# cryobondr-qbit2-aqc-rev2.net
KiCad netlist of a schematic drawn in EAGLE
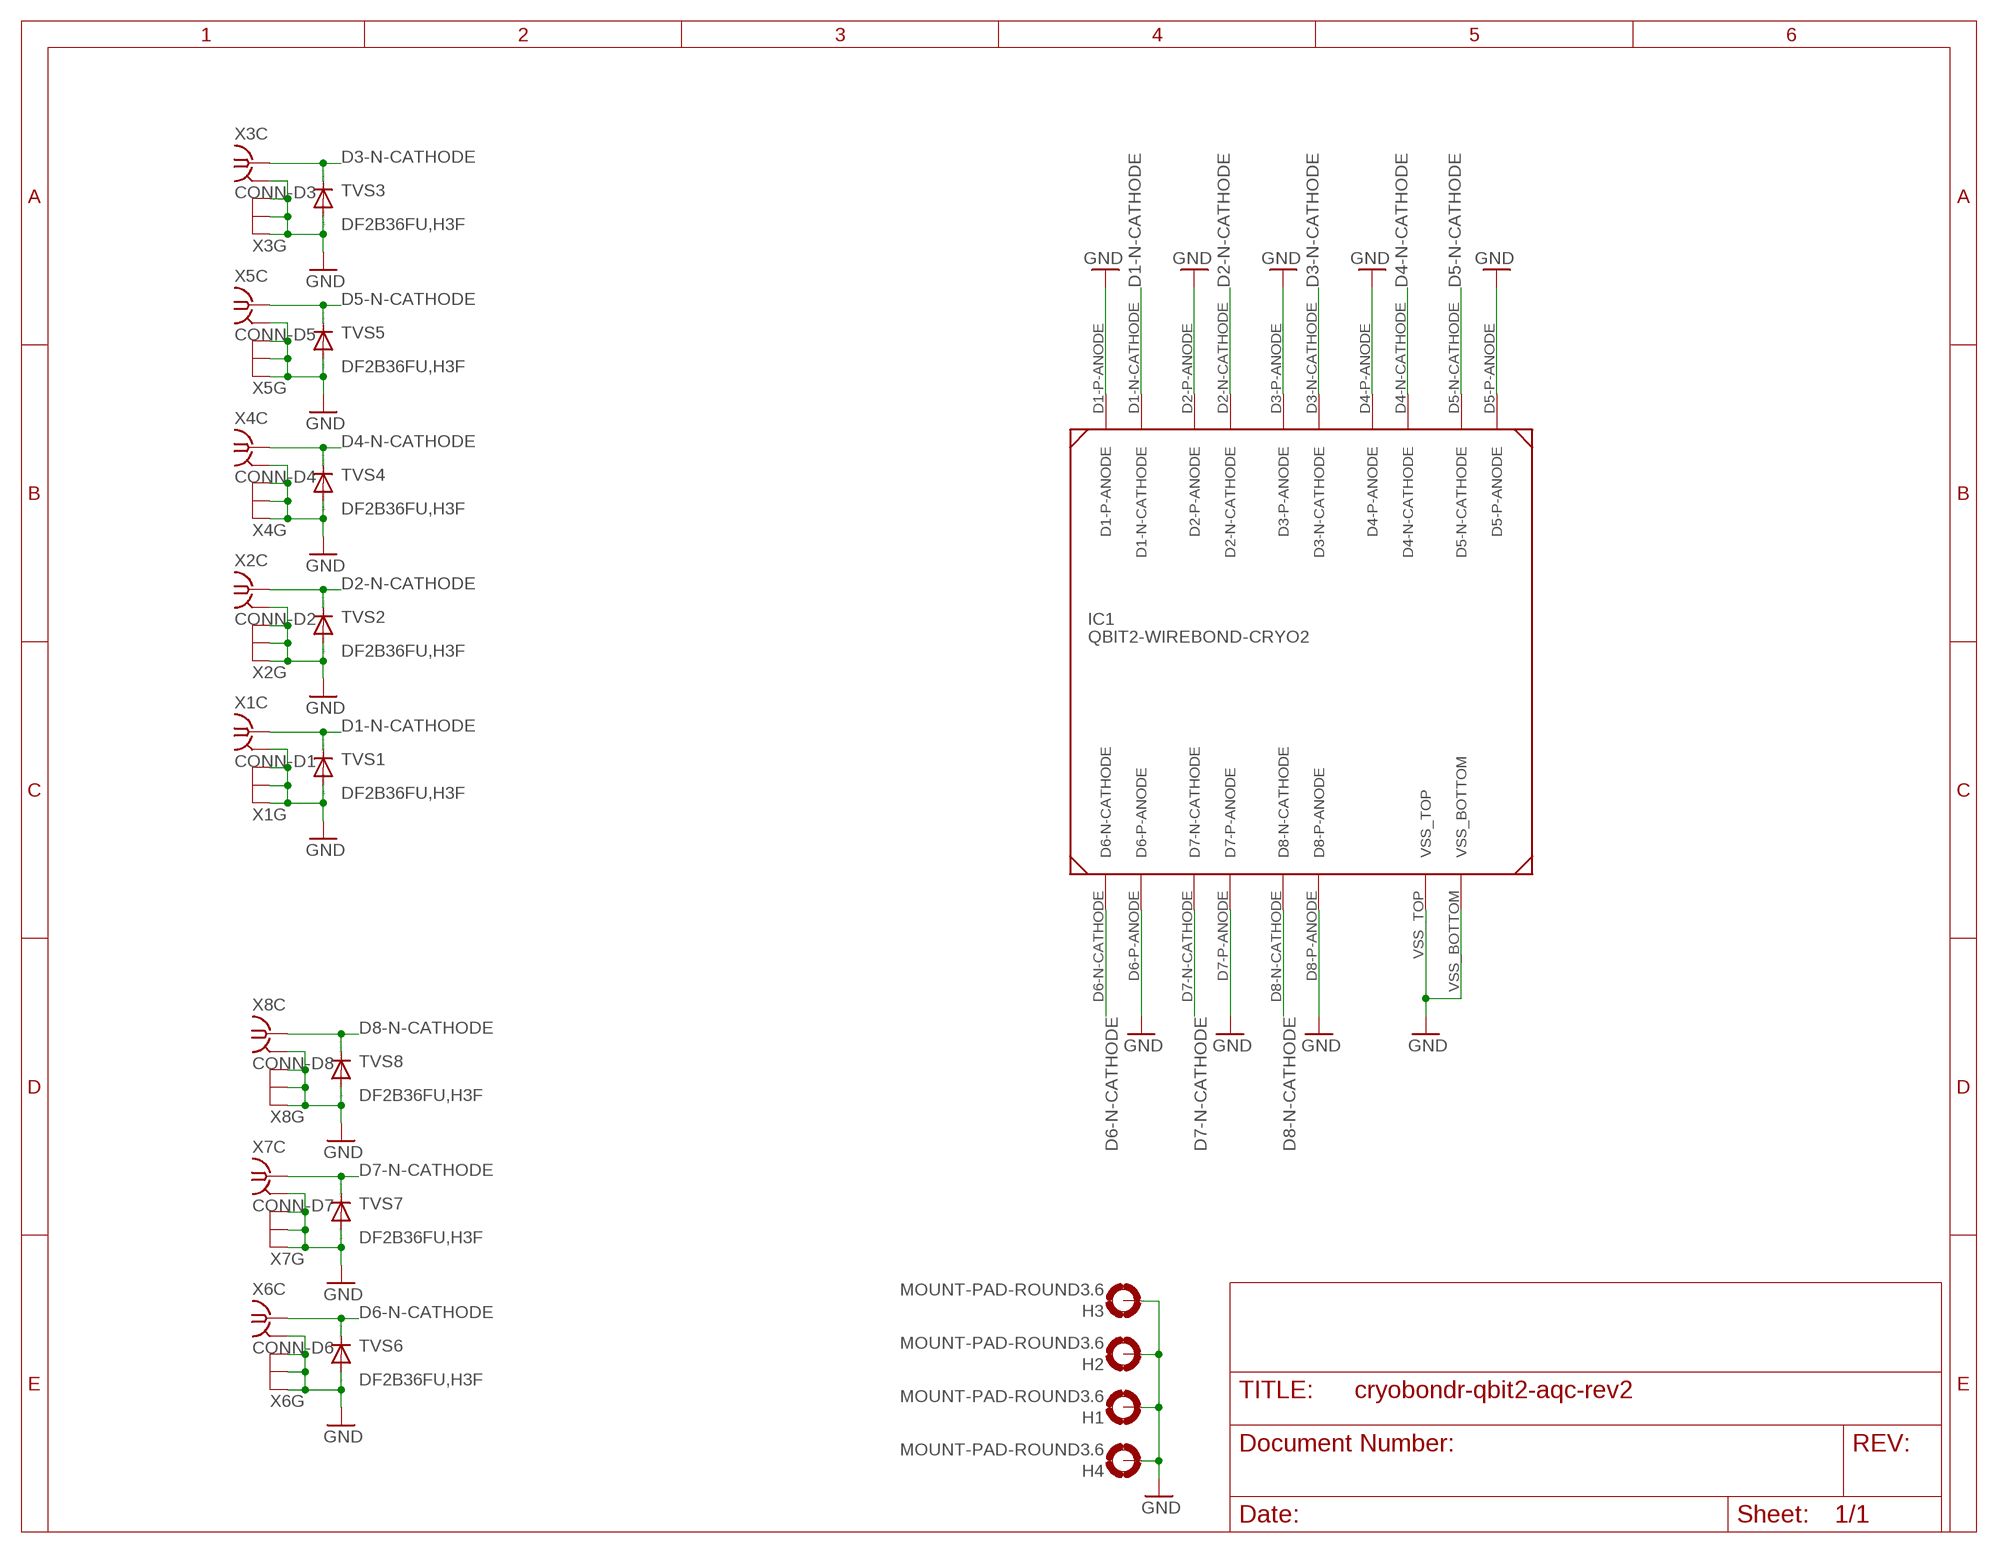
[diagram p0: schematic, sheet 1]

(export (version "E")
  (design (tool "Eeschema 10.0.6"))
  (components
    (comp (ref "H1")
      (value "MOUNT-PAD-ROUND3.6")
      (footprint "eagle-import:3,6-PAD")
      (libsource (lib "eagle-import") (part "MOUNT-PAD-ROUND3.6"))
    )
    (comp (ref "H2")
      (value "MOUNT-PAD-ROUND3.6")
      (footprint "eagle-import:3,6-PAD")
      (libsource (lib "eagle-import") (part "MOUNT-PAD-ROUND3.6"))
    )
    (comp (ref "H3")
      (value "MOUNT-PAD-ROUND3.6")
      (footprint "eagle-import:3,6-PAD")
      (libsource (lib "eagle-import") (part "MOUNT-PAD-ROUND3.6"))
    )
    (comp (ref "H4")
      (value "MOUNT-PAD-ROUND3.6")
      (footprint "eagle-import:3,6-PAD")
      (libsource (lib "eagle-import") (part "MOUNT-PAD-ROUND3.6"))
    )
    (comp (ref "IC1")
      (value "QBIT2-WIREBOND-CRYO2")
      (footprint "eagle-import:QBIT2-WIREBOND-CRYO2")
      (libsource (lib "eagle-import") (part "QBIT2-WIREBOND-CRYO2"))
    )
    (comp (ref "TVS1")
      (value "DF2B36FU,H3F")
      (footprint "eagle-import:SOD323-R")
      (libsource (lib "eagle-import") (part "DIODE-SOD323-R"))
    )
    (comp (ref "TVS2")
      (value "DF2B36FU,H3F")
      (footprint "eagle-import:SOD323-R")
      (libsource (lib "eagle-import") (part "DIODE-SOD323-R"))
    )
    (comp (ref "TVS3")
      (value "DF2B36FU,H3F")
      (footprint "eagle-import:SOD323-R")
      (libsource (lib "eagle-import") (part "DIODE-SOD323-R"))
    )
    (comp (ref "TVS4")
      (value "DF2B36FU,H3F")
      (footprint "eagle-import:SOD323-R")
      (libsource (lib "eagle-import") (part "DIODE-SOD323-R"))
    )
    (comp (ref "TVS5")
      (value "DF2B36FU,H3F")
      (footprint "eagle-import:SOD323-R")
      (libsource (lib "eagle-import") (part "DIODE-SOD323-R"))
    )
    (comp (ref "TVS6")
      (value "DF2B36FU,H3F")
      (footprint "eagle-import:SOD323-R")
      (libsource (lib "eagle-import") (part "DIODE-SOD323-R"))
    )
    (comp (ref "TVS7")
      (value "DF2B36FU,H3F")
      (footprint "eagle-import:SOD323-R")
      (libsource (lib "eagle-import") (part "DIODE-SOD323-R"))
    )
    (comp (ref "TVS8")
      (value "DF2B36FU,H3F")
      (footprint "eagle-import:SOD323-R")
      (libsource (lib "eagle-import") (part "DIODE-SOD323-R"))
    )
    (comp (ref "X1")
      (value "CONN-D1")
      (footprint "eagle-import:MMCX-SMT-BIGPADS")
      (libsource (lib "eagle-import") (part "MMCXBIGPAD"))
    )
    (comp (ref "X2")
      (value "CONN-D2")
      (footprint "eagle-import:MMCX-SMT-BIGPADS")
      (libsource (lib "eagle-import") (part "MMCXBIGPAD"))
    )
    (comp (ref "X3")
      (value "CONN-D3")
      (footprint "eagle-import:MMCX-SMT-BIGPADS")
      (libsource (lib "eagle-import") (part "MMCXBIGPAD"))
    )
    (comp (ref "X4")
      (value "CONN-D4")
      (footprint "eagle-import:MMCX-SMT-BIGPADS")
      (libsource (lib "eagle-import") (part "MMCXBIGPAD"))
    )
    (comp (ref "X5")
      (value "CONN-D5")
      (footprint "eagle-import:MMCX-SMT-BIGPADS")
      (libsource (lib "eagle-import") (part "MMCXBIGPAD"))
    )
    (comp (ref "X6")
      (value "CONN-D6")
      (footprint "eagle-import:MMCX-SMT-BIGPADS")
      (libsource (lib "eagle-import") (part "MMCXBIGPAD"))
    )
    (comp (ref "X7")
      (value "CONN-D7")
      (footprint "eagle-import:MMCX-SMT-BIGPADS")
      (libsource (lib "eagle-import") (part "MMCXBIGPAD"))
    )
    (comp (ref "X8")
      (value "CONN-D8")
      (footprint "eagle-import:MMCX-SMT-BIGPADS")
      (libsource (lib "eagle-import") (part "MMCXBIGPAD"))
    )
  )
  (nets
    (net (code "1") (name "/D1-N-CATHODE") (class "Default")
      (node (ref "IC1") (pin "D1-N-CATHODE") (pinfunction "D1-N-CATHODE_D1-N-CATHODE") (pintype "bidirectional"))
      (node (ref "TVS1") (pin "C") (pinfunction "C_C") (pintype "passive"))
      (node (ref "X1") (pin "S") (pinfunction "1_S") (pintype "passive"))
    )
    (net (code "2") (name "/D2-N-CATHODE") (class "Default")
      (node (ref "IC1") (pin "D2-N-CATHODE") (pinfunction "D2-N-CATHODE_D2-N-CATHODE") (pintype "bidirectional"))
      (node (ref "TVS2") (pin "C") (pinfunction "C_C") (pintype "passive"))
      (node (ref "X2") (pin "S") (pinfunction "1_S") (pintype "passive"))
    )
    (net (code "3") (name "/D3-N-CATHODE") (class "Default")
      (node (ref "IC1") (pin "D3-N-CATHODE") (pinfunction "D3-N-CATHODE_D3-N-CATHODE") (pintype "bidirectional"))
      (node (ref "TVS3") (pin "C") (pinfunction "C_C") (pintype "passive"))
      (node (ref "X3") (pin "S") (pinfunction "1_S") (pintype "passive"))
    )
    (net (code "4") (name "/D4-N-CATHODE") (class "Default")
      (node (ref "IC1") (pin "D4-N-CATHODE") (pinfunction "D4-N-CATHODE_D4-N-CATHODE") (pintype "bidirectional"))
      (node (ref "TVS4") (pin "C") (pinfunction "C_C") (pintype "passive"))
      (node (ref "X4") (pin "S") (pinfunction "1_S") (pintype "passive"))
    )
    (net (code "5") (name "/D5-N-CATHODE") (class "Default")
      (node (ref "IC1") (pin "D5-N-CATHODE") (pinfunction "D5-N-CATHODE_D5-N-CATHODE") (pintype "bidirectional"))
      (node (ref "TVS5") (pin "C") (pinfunction "C_C") (pintype "passive"))
      (node (ref "X5") (pin "S") (pinfunction "1_S") (pintype "passive"))
    )
    (net (code "6") (name "/D6-N-CATHODE") (class "Default")
      (node (ref "IC1") (pin "D6-N-CATHODE") (pinfunction "D6-N-CATHODE_D6-N-CATHODE") (pintype "bidirectional"))
      (node (ref "TVS6") (pin "C") (pinfunction "C_C") (pintype "passive"))
      (node (ref "X6") (pin "S") (pinfunction "1_S") (pintype "passive"))
    )
    (net (code "7") (name "/D7-N-CATHODE") (class "Default")
      (node (ref "IC1") (pin "D7-N-CATHODE") (pinfunction "D7-N-CATHODE_D7-N-CATHODE") (pintype "bidirectional"))
      (node (ref "TVS7") (pin "C") (pinfunction "C_C") (pintype "passive"))
      (node (ref "X7") (pin "S") (pinfunction "1_S") (pintype "passive"))
    )
    (net (code "8") (name "/D8-N-CATHODE") (class "Default")
      (node (ref "IC1") (pin "D8-N-CATHODE") (pinfunction "D8-N-CATHODE_D8-N-CATHODE") (pintype "bidirectional"))
      (node (ref "TVS8") (pin "C") (pinfunction "C_C") (pintype "passive"))
      (node (ref "X8") (pin "S") (pinfunction "1_S") (pintype "passive"))
    )
    (net (code "9") (name "GND") (class "Default")
      (node (ref "H1") (pin "B3,6") (pinfunction "MOUNT_B3,6") (pintype "passive"))
      (node (ref "H2") (pin "B3,6") (pinfunction "MOUNT_B3,6") (pintype "passive"))
      (node (ref "H3") (pin "B3,6") (pinfunction "MOUNT_B3,6") (pintype "passive"))
      (node (ref "H4") (pin "B3,6") (pinfunction "MOUNT_B3,6") (pintype "passive"))
      (node (ref "IC1") (pin "D1-P-ANODE") (pinfunction "D1-P-ANODE_D1-P-ANODE") (pintype "bidirectional"))
      (node (ref "IC1") (pin "D2-P-ANODE") (pinfunction "D2-P-ANODE_D2-P-ANODE") (pintype "bidirectional"))
      (node (ref "IC1") (pin "D3-P-ANODE") (pinfunction "D3-P-ANODE_D3-P-ANODE") (pintype "bidirectional"))
      (node (ref "IC1") (pin "D4-P-ANODE") (pinfunction "D4-P-ANODE_D4-P-ANODE") (pintype "bidirectional"))
      (node (ref "IC1") (pin "D5-P-ANODE") (pinfunction "D5-P-ANODE_D5-P-ANODE") (pintype "bidirectional"))
      (node (ref "IC1") (pin "D6-P-ANODE") (pinfunction "D6-P-ANODE_D6-P-ANODE") (pintype "bidirectional"))
      (node (ref "IC1") (pin "D7-P-ANODE") (pinfunction "D7-P-ANODE_D7-P-ANODE") (pintype "bidirectional"))
      (node (ref "IC1") (pin "D8-P-ANODE") (pinfunction "D8-P-ANODE_D8-P-ANODE") (pintype "bidirectional"))
      (node (ref "IC1") (pin "VSS_BOTTOM") (pinfunction "VSS_BOTTOM_VSS_BOTTOM") (pintype "bidirectional"))
      (node (ref "IC1") (pin "VSS_TOP") (pinfunction "VSS_TOP_VSS_TOP") (pintype "bidirectional"))
      (node (ref "TVS1") (pin "A") (pinfunction "A_A") (pintype "passive"))
      (node (ref "TVS2") (pin "A") (pinfunction "A_A") (pintype "passive"))
      (node (ref "TVS3") (pin "A") (pinfunction "A_A") (pintype "passive"))
      (node (ref "TVS4") (pin "A") (pinfunction "A_A") (pintype "passive"))
      (node (ref "TVS5") (pin "A") (pinfunction "A_A") (pintype "passive"))
      (node (ref "TVS6") (pin "A") (pinfunction "A_A") (pintype "passive"))
      (node (ref "TVS7") (pin "A") (pinfunction "A_A") (pintype "passive"))
      (node (ref "TVS8") (pin "A") (pinfunction "A_A") (pintype "passive"))
      (node (ref "X1") (pin "G1") (pinfunction "GND_G1") (pintype "power_in"))
      (node (ref "X1") (pin "G2") (pinfunction "GND_G2") (pintype "power_in"))
      (node (ref "X1") (pin "G3") (pinfunction "GND_G3") (pintype "power_in"))
      (node (ref "X1") (pin "G4") (pinfunction "GND_G4") (pintype "power_in"))
      (node (ref "X2") (pin "G1") (pinfunction "GND_G1") (pintype "power_in"))
      (node (ref "X2") (pin "G2") (pinfunction "GND_G2") (pintype "power_in"))
      (node (ref "X2") (pin "G3") (pinfunction "GND_G3") (pintype "power_in"))
      (node (ref "X2") (pin "G4") (pinfunction "GND_G4") (pintype "power_in"))
      (node (ref "X3") (pin "G1") (pinfunction "GND_G1") (pintype "power_in"))
      (node (ref "X3") (pin "G2") (pinfunction "GND_G2") (pintype "power_in"))
      (node (ref "X3") (pin "G3") (pinfunction "GND_G3") (pintype "power_in"))
      (node (ref "X3") (pin "G4") (pinfunction "GND_G4") (pintype "power_in"))
      (node (ref "X4") (pin "G1") (pinfunction "GND_G1") (pintype "power_in"))
      (node (ref "X4") (pin "G2") (pinfunction "GND_G2") (pintype "power_in"))
      (node (ref "X4") (pin "G3") (pinfunction "GND_G3") (pintype "power_in"))
      (node (ref "X4") (pin "G4") (pinfunction "GND_G4") (pintype "power_in"))
      (node (ref "X5") (pin "G1") (pinfunction "GND_G1") (pintype "power_in"))
      (node (ref "X5") (pin "G2") (pinfunction "GND_G2") (pintype "power_in"))
      (node (ref "X5") (pin "G3") (pinfunction "GND_G3") (pintype "power_in"))
      (node (ref "X5") (pin "G4") (pinfunction "GND_G4") (pintype "power_in"))
      (node (ref "X6") (pin "G1") (pinfunction "GND_G1") (pintype "power_in"))
      (node (ref "X6") (pin "G2") (pinfunction "GND_G2") (pintype "power_in"))
      (node (ref "X6") (pin "G3") (pinfunction "GND_G3") (pintype "power_in"))
      (node (ref "X6") (pin "G4") (pinfunction "GND_G4") (pintype "power_in"))
      (node (ref "X7") (pin "G1") (pinfunction "GND_G1") (pintype "power_in"))
      (node (ref "X7") (pin "G2") (pinfunction "GND_G2") (pintype "power_in"))
      (node (ref "X7") (pin "G3") (pinfunction "GND_G3") (pintype "power_in"))
      (node (ref "X7") (pin "G4") (pinfunction "GND_G4") (pintype "power_in"))
      (node (ref "X8") (pin "G1") (pinfunction "GND_G1") (pintype "power_in"))
      (node (ref "X8") (pin "G2") (pinfunction "GND_G2") (pintype "power_in"))
      (node (ref "X8") (pin "G3") (pinfunction "GND_G3") (pintype "power_in"))
      (node (ref "X8") (pin "G4") (pinfunction "GND_G4") (pintype "power_in"))
    )
  )
)
